# SCH_PCB_sin_SMD-v1_2026-09-21.net
KiCad netlist of a schematic drawn in EasyEDA
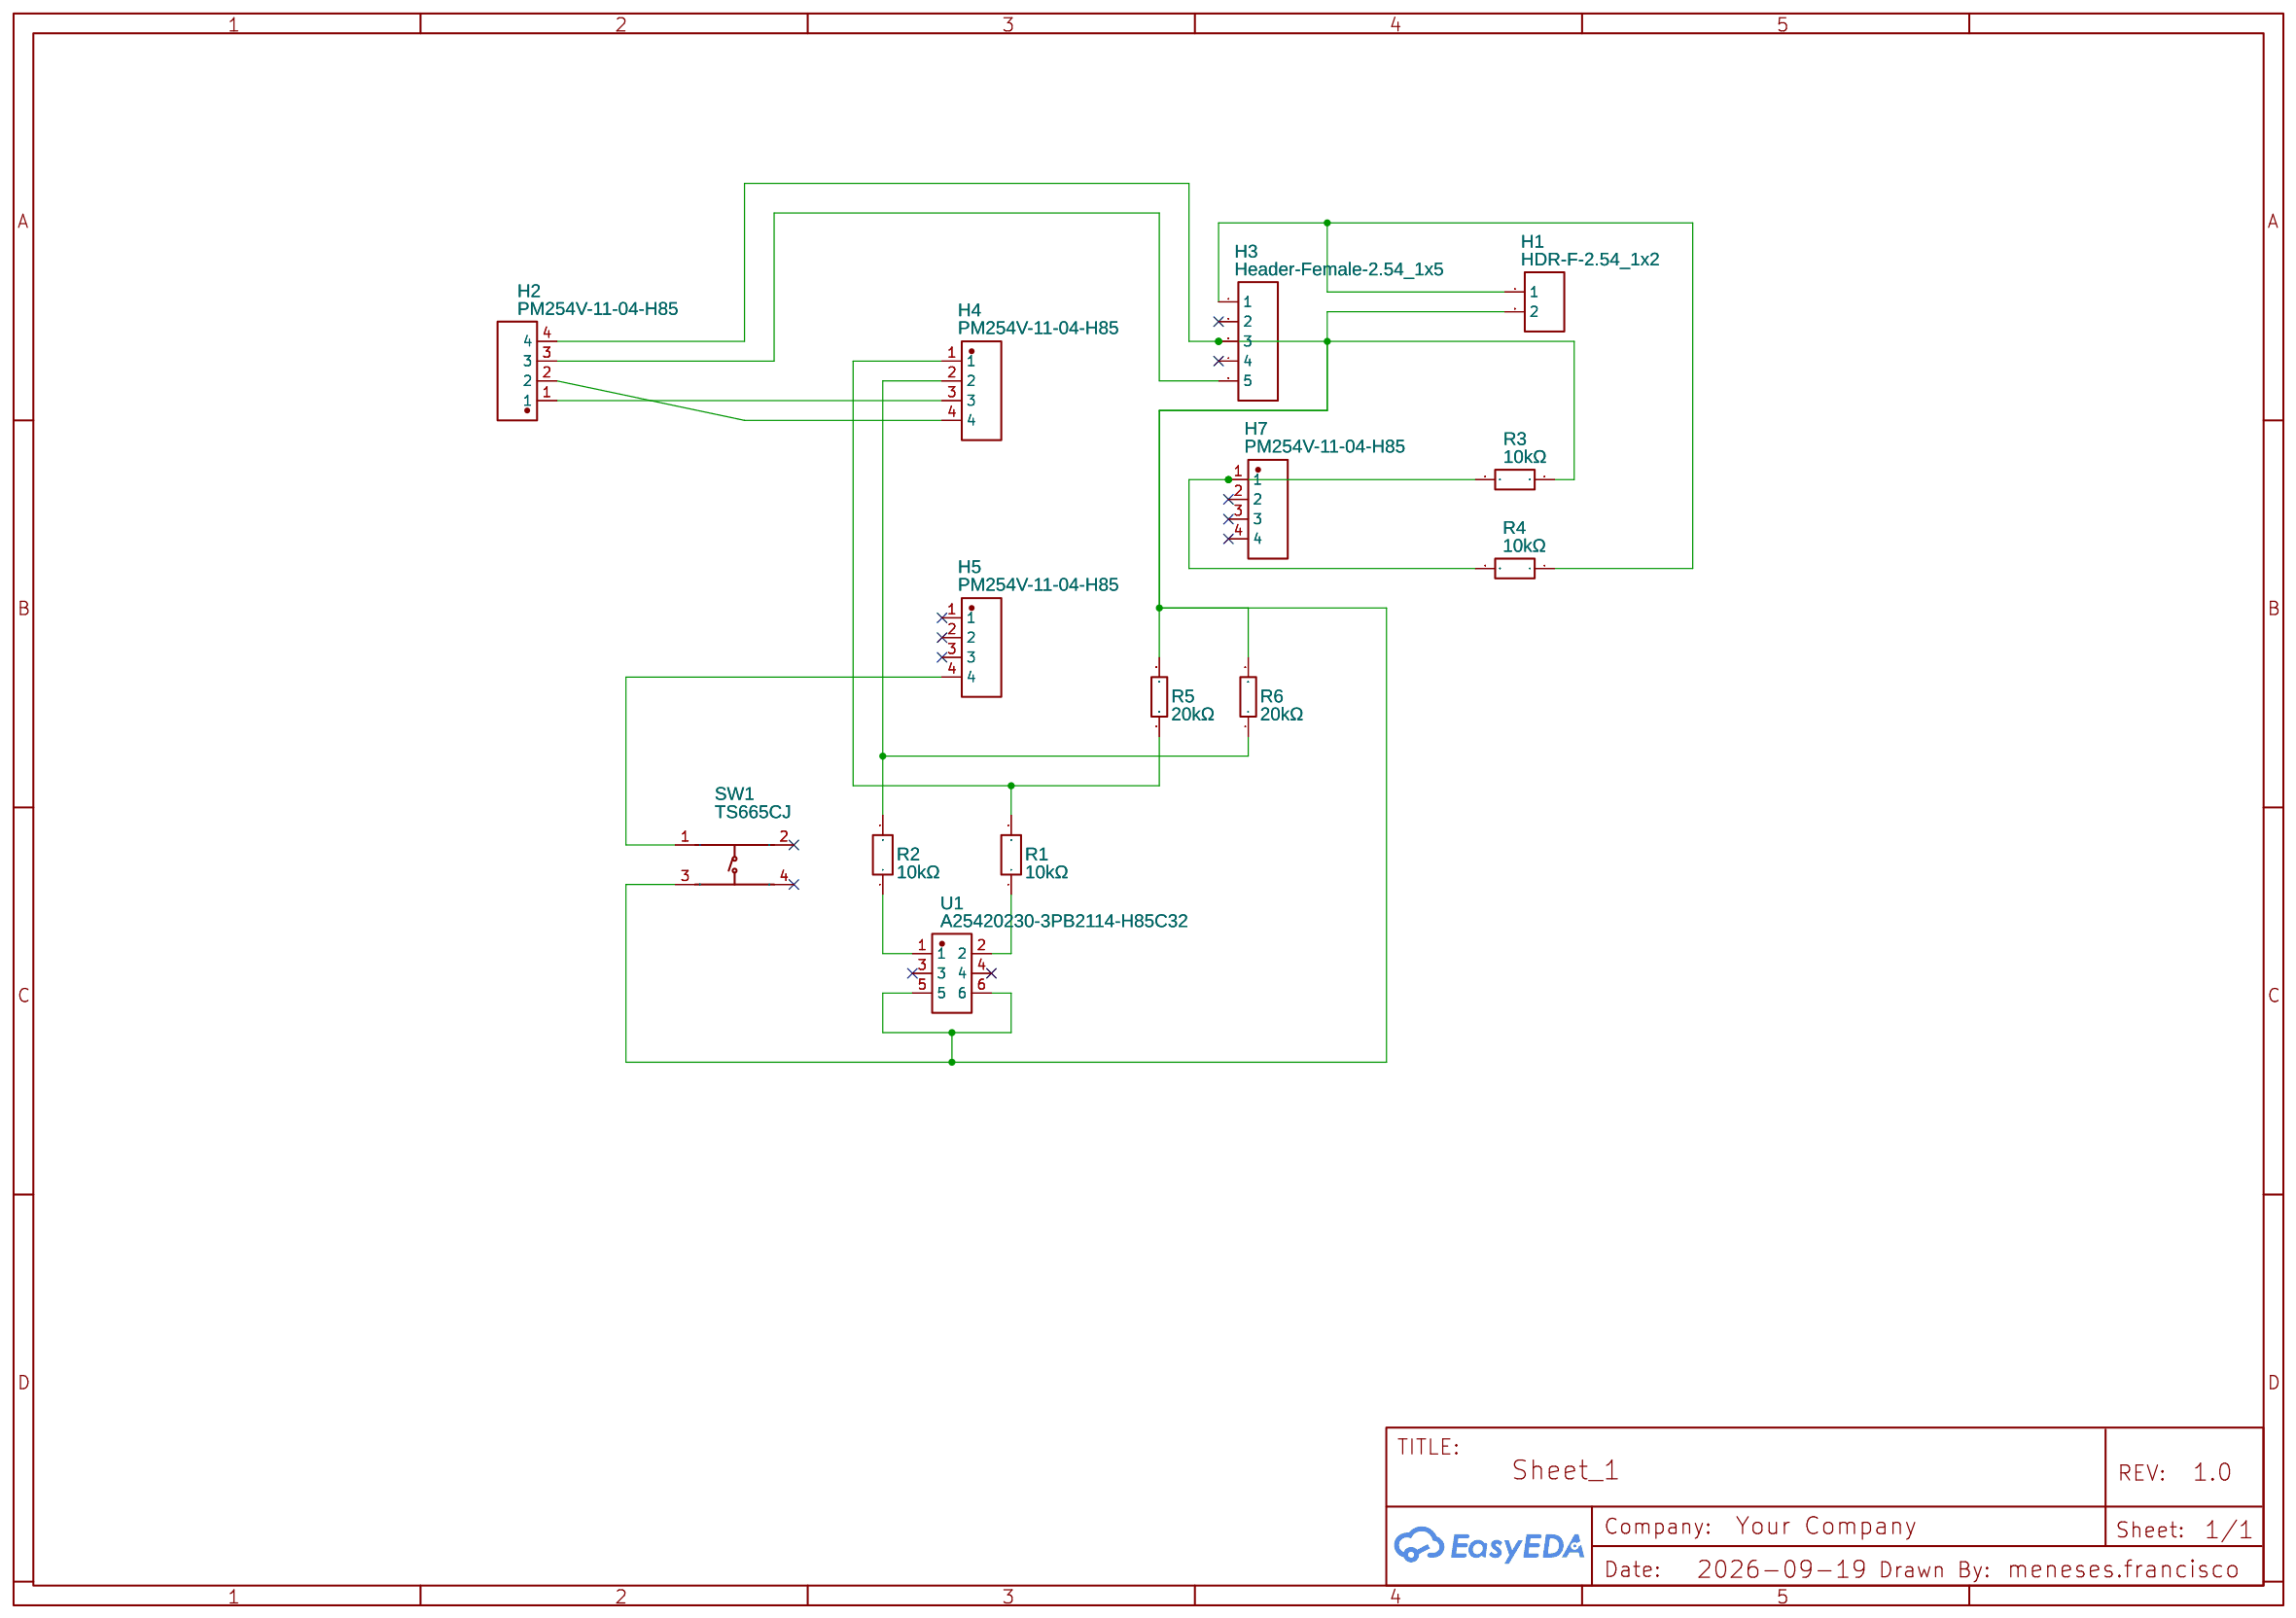
[diagram p0: schematic sheet]

(export (version "E")
  (design (tool "Eeschema 10.0.6"))
  (components
    (comp (ref "H1") (value "HDR-F-2.54_1x2") (libsource (lib "") (part "HDR-F-2.54_1x2")))
    (comp (ref "H2")
      (value "PM254V-11-04-H85")
      (fields (field (name "Manufacturer") "XFCN(兴飞)"))
      (libsource (lib "") (part "PM254V-11-04-H85_1"))
    )
    (comp (ref "H3")
      (value "Header-Female-2.54_1x5")
      (fields (field (name "Manufacturer Part") "2.54-1*5P母") (field (name "Manufacturer") "BOOMELE(博穆精密)"))
      (libsource (lib "") (part "Header-Female-2.54_1x5"))
    )
    (comp (ref "H4")
      (value "PM254V-11-04-H85")
      (fields (field (name "Manufacturer") "XFCN(兴飞)"))
      (libsource (lib "") (part "PM254V-11-04-H85"))
    )
    (comp (ref "H5")
      (value "PM254V-11-04-H85")
      (fields (field (name "Manufacturer") "XFCN(兴飞)"))
      (libsource (lib "") (part "PM254V-11-04-H85"))
    )
    (comp (ref "H7")
      (value "PM254V-11-04-H85")
      (fields (field (name "Manufacturer") "XFCN(兴飞)"))
      (libsource (lib "") (part "PM254V-11-04-H85"))
    )
    (comp (ref "R1")
      (value "10kΩ")
      (fields (field (name "Manufacturer Part") "MF1/4W-10K±1%-ST52") (field (name "Manufacturer") "VO(翔胜)"))
      (libsource (lib "") (part "MF1/4W-10K±1%-ST52"))
    )
    (comp (ref "R2")
      (value "10kΩ")
      (fields (field (name "Manufacturer Part") "MF1/4W-10K±1%-ST52") (field (name "Manufacturer") "VO(翔胜)"))
      (libsource (lib "") (part "MF1/4W-10K±1%-ST52"))
    )
    (comp (ref "R3")
      (value "10kΩ")
      (fields (field (name "Manufacturer Part") "MF1/4W-10K±1%-ST52") (field (name "Manufacturer") "VO(翔胜)"))
      (libsource (lib "") (part "MF1/4W-10K±1%-ST52_1"))
    )
    (comp (ref "R4")
      (value "10kΩ")
      (fields (field (name "Manufacturer Part") "MF1/4W-10K±1%-ST52") (field (name "Manufacturer") "VO(翔胜)"))
      (libsource (lib "") (part "MF1/4W-10K±1%-ST52_1"))
    )
    (comp (ref "R5")
      (value "20kΩ")
      (fields (field (name "Manufacturer Part") "MF1/4W-20KΩ±1% T") (field (name "Manufacturer") "CCO(千志电子)"))
      (libsource (lib "") (part "MF1/4W-20KΩ±1% T52"))
    )
    (comp (ref "R6")
      (value "20kΩ")
      (fields (field (name "Manufacturer Part") "MF1/4W-20KΩ±1% T") (field (name "Manufacturer") "CCO(千志电子)"))
      (libsource (lib "") (part "MF1/4W-20KΩ±1% T52"))
    )
    (comp (ref "SW1")
      (value "TS665CJ")
      (fields (field (name "Manufacturer") "SHOU HAN(首韩)"))
      (libsource (lib "") (part "TS665CJ"))
    )
    (comp (ref "U1")
      (value "A25420230-3PB2114-H85C32")
      (fields (field (name "Manufacturer") "HMTCONN(华明通)"))
      (libsource (lib "") (part "A25420230-3PB2114-H85C32"))
    )
  )
  (nets
    (net (code "1") (name "Net-(H1-Pad1)") (class "Default")
      (node (ref "H1") (pin "1") (pinfunction "1_1") (pintype "input"))
      (node (ref "H3") (pin "1") (pinfunction "1_1") (pintype "input"))
      (node (ref "R4") (pin "1") (pinfunction "1_1") (pintype "unspecified"))
    )
    (net (code "2") (name "Net-(H2-Pad1)") (class "Default")
      (node (ref "H2") (pin "1") (pinfunction "1_1") (pintype "unspecified"))
      (node (ref "H4") (pin "3") (pinfunction "3_3") (pintype "unspecified"))
    )
    (net (code "3") (name "Net-(H2-Pad2)") (class "Default")
      (node (ref "H2") (pin "2") (pinfunction "2_2") (pintype "unspecified"))
      (node (ref "H4") (pin "4") (pinfunction "4_4") (pintype "unspecified"))
    )
    (net (code "4") (name "Net-(H2-Pad3)") (class "Default")
      (node (ref "H2") (pin "3") (pinfunction "3_3") (pintype "unspecified"))
      (node (ref "H3") (pin "5") (pinfunction "5_5") (pintype "input"))
    )
    (net (code "5") (name "Net-(H4-Pad1)") (class "Default")
      (node (ref "H4") (pin "1") (pinfunction "1_1") (pintype "unspecified"))
      (node (ref "R1") (pin "2") (pinfunction "2_2") (pintype "unspecified"))
      (node (ref "R5") (pin "1") (pinfunction "1_1") (pintype "unspecified"))
    )
    (net (code "6") (name "Net-(H4-Pad2)") (class "Default")
      (node (ref "H4") (pin "2") (pinfunction "2_2") (pintype "unspecified"))
      (node (ref "R2") (pin "2") (pinfunction "2_2") (pintype "unspecified"))
      (node (ref "R6") (pin "1") (pinfunction "1_1") (pintype "unspecified"))
    )
    (net (code "7") (name "Net-(H7-Pad1)") (class "Default")
      (node (ref "H7") (pin "1") (pinfunction "1_1") (pintype "unspecified"))
      (node (ref "R3") (pin "2") (pinfunction "2_2") (pintype "unspecified"))
      (node (ref "R4") (pin "2") (pinfunction "2_2") (pintype "unspecified"))
    )
    (net (code "8") (name "Net-(R1-Pad1)") (class "Default")
      (node (ref "R1") (pin "1") (pinfunction "1_1") (pintype "unspecified"))
      (node (ref "U1") (pin "2") (pinfunction "2_2") (pintype "unspecified"))
    )
    (net (code "9") (name "Net-(R2-Pad1)") (class "Default")
      (node (ref "R2") (pin "1") (pinfunction "1_1") (pintype "unspecified"))
      (node (ref "U1") (pin "1") (pinfunction "1_1") (pintype "unspecified"))
    )
    (net (code "10") (name "Net-(SW1-A)") (class "Default")
      (node (ref "H5") (pin "4") (pinfunction "4_4") (pintype "unspecified"))
      (node (ref "SW1") (pin "1") (pinfunction "A_1") (pintype "unspecified"))
    )
    (net (code "11") (name "Net-(SW1-C)") (class "Default")
      (node (ref "H1") (pin "2") (pinfunction "2_2") (pintype "input"))
      (node (ref "H2") (pin "4") (pinfunction "4_4") (pintype "unspecified"))
      (node (ref "H3") (pin "3") (pinfunction "3_3") (pintype "input"))
      (node (ref "R3") (pin "1") (pinfunction "1_1") (pintype "unspecified"))
      (node (ref "R5") (pin "2") (pinfunction "2_2") (pintype "unspecified"))
      (node (ref "R6") (pin "2") (pinfunction "2_2") (pintype "unspecified"))
      (node (ref "SW1") (pin "3") (pinfunction "C_3") (pintype "unspecified"))
      (node (ref "U1") (pin "5") (pinfunction "5_5") (pintype "unspecified"))
      (node (ref "U1") (pin "6") (pinfunction "6_6") (pintype "unspecified"))
    )
    (net (code "12") (name "unconnected-(H3-Pad2)") (class "Default")
      (node (ref "H3") (pin "2") (pinfunction "2_2") (pintype "input+no_connect"))
    )
    (net (code "13") (name "unconnected-(H3-Pad4)") (class "Default")
      (node (ref "H3") (pin "4") (pinfunction "4_4") (pintype "input+no_connect"))
    )
    (net (code "14") (name "unconnected-(H5-Pad1)") (class "Default")
      (node (ref "H5") (pin "1") (pinfunction "1_1") (pintype "unspecified+no_connect"))
    )
    (net (code "15") (name "unconnected-(H5-Pad2)") (class "Default")
      (node (ref "H5") (pin "2") (pinfunction "2_2") (pintype "unspecified+no_connect"))
    )
    (net (code "16") (name "unconnected-(H5-Pad3)") (class "Default")
      (node (ref "H5") (pin "3") (pinfunction "3_3") (pintype "unspecified+no_connect"))
    )
    (net (code "17") (name "unconnected-(H7-Pad2)") (class "Default")
      (node (ref "H7") (pin "2") (pinfunction "2_2") (pintype "unspecified+no_connect"))
    )
    (net (code "18") (name "unconnected-(H7-Pad3)") (class "Default")
      (node (ref "H7") (pin "3") (pinfunction "3_3") (pintype "unspecified+no_connect"))
    )
    (net (code "19") (name "unconnected-(H7-Pad4)") (class "Default")
      (node (ref "H7") (pin "4") (pinfunction "4_4") (pintype "unspecified+no_connect"))
    )
    (net (code "20") (name "unconnected-(SW1-B-Pad2)") (class "Default")
      (node (ref "SW1") (pin "2") (pinfunction "B_2") (pintype "unspecified+no_connect"))
    )
    (net (code "21") (name "unconnected-(SW1-D-Pad4)") (class "Default")
      (node (ref "SW1") (pin "4") (pinfunction "D_4") (pintype "unspecified+no_connect"))
    )
    (net (code "22") (name "unconnected-(U1-Pad3)") (class "Default")
      (node (ref "U1") (pin "3") (pinfunction "3_3") (pintype "unspecified+no_connect"))
    )
    (net (code "23") (name "unconnected-(U1-Pad4)") (class "Default")
      (node (ref "U1") (pin "4") (pinfunction "4_4") (pintype "unspecified+no_connect"))
    )
  )
)
